# Encoder_BR.net
KiCad netlist of a schematic drawn in Altium Designer
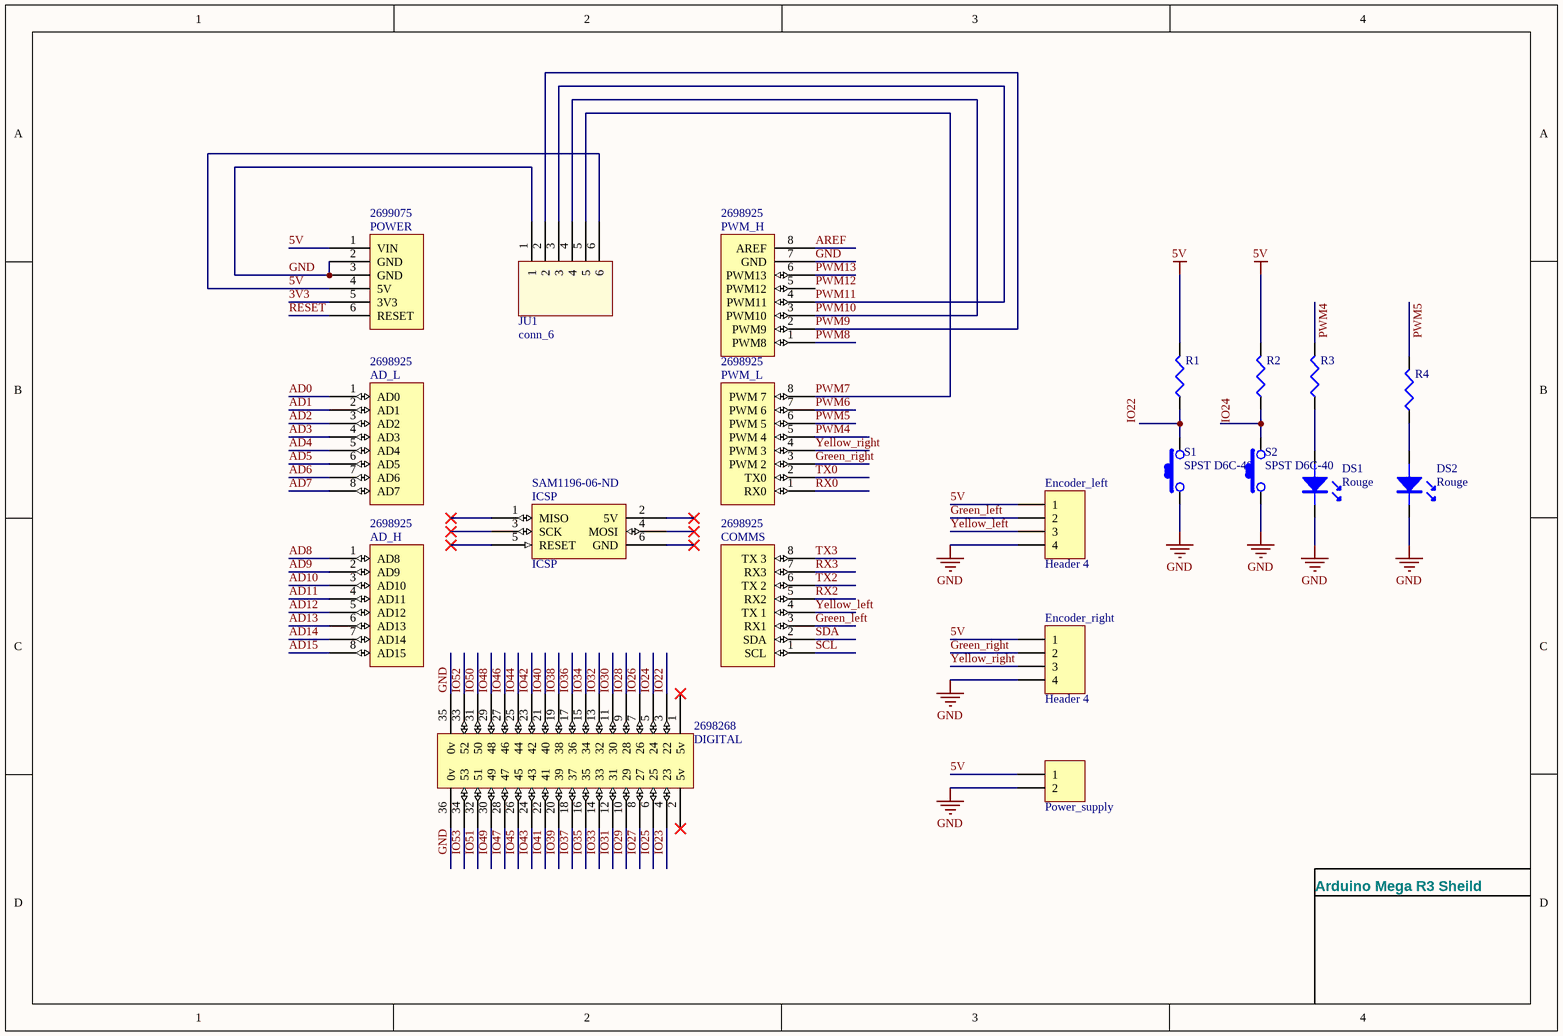
[diagram p0: Encoder_BR.SchDoc]

(export (version "E")
  (design (tool "Eeschema 10.0.6"))
  (components
    (comp (ref "AD_H")
      (value "AD_H")
      (footprint "Header 8x1 8.5mm")
      (fields (field (name "SUPPLIER PART NUMBER 4") "2698925"))
      (libsource (lib "Header") (part "AD_H"))
    )
    (comp (ref "AD_L")
      (value "AD_L")
      (footprint "Header 8x1 8.5mm")
      (fields (field (name "SUPPLIER PART NUMBER 5") "2698925"))
      (libsource (lib "Header") (part "AD_L"))
    )
    (comp (ref "COMMS")
      (value "Communication")
      (footprint "Header 8x1 8.5mm")
      (fields (field (name "SUPPLIER PART NUMBER 4") "2698925"))
      (libsource (lib "Header") (part "Communication"))
    )
    (comp (ref "DIGITAL")
      (value "IO_36")
      (footprint "HEADER 36X 8MM")
      (fields (field (name "SUPPLIER PART NUMBER 5") "2698268"))
      (libsource (lib "Header") (part "IO_36"))
    )
    (comp (ref "DS1")
      (value "LED")
      (footprint "LED 0.1")
      (fields (field (name "COLOR") "Rouge") (field (name "DESIGNER") "ECAM 2004"))
      (libsource (lib "ECAM") (part "LED"))
    )
    (comp (ref "DS2")
      (value "LED")
      (footprint "LED 0.1")
      (fields (field (name "COLOR") "Rouge") (field (name "DESIGNER") "ECAM 2004"))
      (libsource (lib "ECAM") (part "LED"))
    )
    (comp (ref "Encoder_left")
      (value "Header 4")
      (footprint "Header_4")
      (description "Header, 4-Pin")
      (fields (field (name "PUBLISHER") "Altium Limited"))
      (libsource (lib "Eurobot_lib") (part "Header 4"))
    )
    (comp (ref "Encoder_right")
      (value "Header 4")
      (footprint "Header_4")
      (description "Header, 4-Pin")
      (fields (field (name "PUBLISHER") "Altium Limited"))
      (libsource (lib "Eurobot_lib") (part "Header 4"))
    )
    (comp (ref "ICSP")
      (value "ICSP")
      (footprint "ICSP")
      (fields (field (name "SUPPLIER PART NUMBER 5") "SAM1196-06-ND"))
      (libsource (lib "Header") (part "ICSP"))
    )
    (comp (ref "JU1")
      (value "conn_6")
      (footprint "conn_6")
      (libsource (lib "Integrated_Library2") (part "conn_6"))
    )
    (comp (ref "POWER")
      (value "POWER")
      (footprint "Header 6x1 8.5mm")
      (fields (field (name "SUPPLIER PART NUMBER 2") "2699075"))
      (libsource (lib "Header") (part "POWER"))
    )
    (comp (ref "Power_supply")
      (value "Connecteur 2")
      (footprint "Header_2")
      (description "Header 2")
      (fields (field (name "DESIGNER") "ECAM 2005"))
      (libsource (lib "Eurobot_lib") (part "Connecteur 2"))
    )
    (comp (ref "PWM_H")
      (value "PWM_H")
      (footprint "Header 8x1 8.5mm")
      (fields (field (name "SUPPLIER PART NUMBER 4") "2698925"))
      (libsource (lib "Header") (part "PWM_H"))
    )
    (comp (ref "PWM_L")
      (value "PWM_L")
      (footprint "Header 8x1 8.5mm")
      (fields (field (name "SUPPLIER PART NUMBER 4") "2698925"))
      (libsource (lib "Header") (part "PWM_L"))
    )
    (comp (ref "R1")
      (value "Résistance")
      (footprint "AXIAL-0.3")
      (description "Résistance standard")
      (fields (field (name "DESIGNER") "ECAM 2005"))
      (libsource (lib "ECAM") (part "Résistance"))
    )
    (comp (ref "R2")
      (value "Résistance")
      (footprint "AXIAL-0.3")
      (description "Résistance standard")
      (fields (field (name "DESIGNER") "ECAM 2005"))
      (libsource (lib "ECAM") (part "Résistance"))
    )
    (comp (ref "R3")
      (value "Résistance")
      (footprint "AXIAL-0.3")
      (description "Résistance standard")
      (fields (field (name "DESIGNER") "ECAM 2005"))
      (libsource (lib "ECAM") (part "Résistance"))
    )
    (comp (ref "R4")
      (value "Résistance")
      (footprint "AXIAL-0.3")
      (description "Résistance standard")
      (fields (field (name "DESIGNER") "ECAM 2005"))
      (libsource (lib "ECAM") (part "Résistance"))
    )
    (comp (ref "S1")
      (value "Bouton Poussoir D6")
      (footprint "BP-D6 SPST")
      (description "Bouton poussoir")
      (fields
        (field (name "MANUFACTURER") "ITT CANON")
        (field (name "TYPE") "SPST D6C-40")
        (field (name "DESIGNER") "ECAM 2004")
      )
      (libsource (lib "ECAM") (part "Bouton Poussoir D6"))
    )
    (comp (ref "S2")
      (value "Bouton Poussoir D6")
      (footprint "BP-D6 SPST")
      (description "Bouton poussoir")
      (fields
        (field (name "MANUFACTURER") "ITT CANON")
        (field (name "TYPE") "SPST D6C-40")
        (field (name "DESIGNER") "ECAM 2004")
      )
      (libsource (lib "ECAM") (part "Bouton Poussoir D6"))
    )
  )
  (nets
    (net (code "1") (name "/3V3") (class "Default")
      (node (ref "POWER") (pin "5") (pinfunction "3V3_5") (pintype "power_in"))
    )
    (net (code "2") (name "/AD0") (class "Default")
      (node (ref "AD_L") (pin "1") (pinfunction "AD0_1") (pintype "bidirectional"))
    )
    (net (code "3") (name "/AD1") (class "Default")
      (node (ref "AD_L") (pin "2") (pinfunction "AD1_2") (pintype "bidirectional"))
    )
    (net (code "4") (name "/AD2") (class "Default")
      (node (ref "AD_L") (pin "3") (pinfunction "AD2_3") (pintype "bidirectional"))
    )
    (net (code "5") (name "/AD3") (class "Default")
      (node (ref "AD_L") (pin "4") (pinfunction "AD3_4") (pintype "bidirectional"))
    )
    (net (code "6") (name "/AD4") (class "Default")
      (node (ref "AD_L") (pin "5") (pinfunction "AD4_5") (pintype "bidirectional"))
    )
    (net (code "7") (name "/AD5") (class "Default")
      (node (ref "AD_L") (pin "6") (pinfunction "AD5_6") (pintype "bidirectional"))
    )
    (net (code "8") (name "/AD6") (class "Default")
      (node (ref "AD_L") (pin "7") (pinfunction "AD6_7") (pintype "bidirectional"))
    )
    (net (code "9") (name "/AD7") (class "Default")
      (node (ref "AD_L") (pin "8") (pinfunction "AD7_8") (pintype "bidirectional"))
    )
    (net (code "10") (name "/AD8") (class "Default")
      (node (ref "AD_H") (pin "1") (pinfunction "AD8_1") (pintype "bidirectional"))
    )
    (net (code "11") (name "/AD9") (class "Default")
      (node (ref "AD_H") (pin "2") (pinfunction "AD9_2") (pintype "bidirectional"))
    )
    (net (code "12") (name "/AD10") (class "Default")
      (node (ref "AD_H") (pin "3") (pinfunction "AD10_3") (pintype "bidirectional"))
    )
    (net (code "13") (name "/AD11") (class "Default")
      (node (ref "AD_H") (pin "4") (pinfunction "AD11_4") (pintype "bidirectional"))
    )
    (net (code "14") (name "/AD12") (class "Default")
      (node (ref "AD_H") (pin "5") (pinfunction "AD12_5") (pintype "bidirectional"))
    )
    (net (code "15") (name "/AD13") (class "Default")
      (node (ref "AD_H") (pin "6") (pinfunction "AD13_6") (pintype "bidirectional"))
    )
    (net (code "16") (name "/AD14") (class "Default")
      (node (ref "AD_H") (pin "7") (pinfunction "AD14_7") (pintype "bidirectional"))
    )
    (net (code "17") (name "/AD15") (class "Default")
      (node (ref "AD_H") (pin "8") (pinfunction "AD15_8") (pintype "bidirectional"))
    )
    (net (code "18") (name "/AREF") (class "Default")
      (node (ref "PWM_H") (pin "8") (pinfunction "AREF_8") (pintype "passive"))
    )
    (net (code "19") (name "/Green_left") (class "Default")
      (node (ref "COMMS") (pin "3") (pinfunction "RX1_3") (pintype "bidirectional"))
      (node (ref "Encoder_left") (pin "2") (pinfunction "2_2") (pintype "passive"))
    )
    (net (code "20") (name "/Green_right") (class "Default")
      (node (ref "Encoder_right") (pin "2") (pinfunction "2_2") (pintype "passive"))
      (node (ref "PWM_L") (pin "3") (pinfunction "PWM_2_3") (pintype "bidirectional"))
    )
    (net (code "21") (name "/IO22") (class "Default")
      (node (ref "DIGITAL") (pin "3") (pinfunction "22_3") (pintype "bidirectional"))
      (node (ref "R1") (pin "1") (pinfunction "1_1") (pintype "passive"))
      (node (ref "S1") (pin "2") (pinfunction "2_2") (pintype "passive"))
    )
    (net (code "22") (name "/IO23") (class "Default")
      (node (ref "DIGITAL") (pin "4") (pinfunction "23_4") (pintype "bidirectional"))
    )
    (net (code "23") (name "/IO24") (class "Default")
      (node (ref "DIGITAL") (pin "5") (pinfunction "24_5") (pintype "bidirectional"))
      (node (ref "R2") (pin "1") (pinfunction "1_1") (pintype "passive"))
      (node (ref "S2") (pin "2") (pinfunction "2_2") (pintype "passive"))
    )
    (net (code "24") (name "/IO25") (class "Default")
      (node (ref "DIGITAL") (pin "6") (pinfunction "25_6") (pintype "bidirectional"))
    )
    (net (code "25") (name "/IO26") (class "Default")
      (node (ref "DIGITAL") (pin "7") (pinfunction "26_7") (pintype "bidirectional"))
    )
    (net (code "26") (name "/IO27") (class "Default")
      (node (ref "DIGITAL") (pin "8") (pinfunction "27_8") (pintype "bidirectional"))
    )
    (net (code "27") (name "/IO28") (class "Default")
      (node (ref "DIGITAL") (pin "9") (pinfunction "28_9") (pintype "bidirectional"))
    )
    (net (code "28") (name "/IO29") (class "Default")
      (node (ref "DIGITAL") (pin "10") (pinfunction "29_10") (pintype "bidirectional"))
    )
    (net (code "29") (name "/IO30") (class "Default")
      (node (ref "DIGITAL") (pin "11") (pinfunction "30_11") (pintype "bidirectional"))
    )
    (net (code "30") (name "/IO31") (class "Default")
      (node (ref "DIGITAL") (pin "12") (pinfunction "31_12") (pintype "bidirectional"))
    )
    (net (code "31") (name "/IO32") (class "Default")
      (node (ref "DIGITAL") (pin "13") (pinfunction "32_13") (pintype "bidirectional"))
    )
    (net (code "32") (name "/IO33") (class "Default")
      (node (ref "DIGITAL") (pin "14") (pinfunction "33_14") (pintype "bidirectional"))
    )
    (net (code "33") (name "/IO34") (class "Default")
      (node (ref "DIGITAL") (pin "15") (pinfunction "34_15") (pintype "bidirectional"))
    )
    (net (code "34") (name "/IO35") (class "Default")
      (node (ref "DIGITAL") (pin "16") (pinfunction "35_16") (pintype "bidirectional"))
    )
    (net (code "35") (name "/IO36") (class "Default")
      (node (ref "DIGITAL") (pin "17") (pinfunction "36_17") (pintype "bidirectional"))
    )
    (net (code "36") (name "/IO37") (class "Default")
      (node (ref "DIGITAL") (pin "18") (pinfunction "37_18") (pintype "bidirectional"))
    )
    (net (code "37") (name "/IO38") (class "Default")
      (node (ref "DIGITAL") (pin "19") (pinfunction "38_19") (pintype "bidirectional"))
    )
    (net (code "38") (name "/IO39") (class "Default")
      (node (ref "DIGITAL") (pin "20") (pinfunction "39_20") (pintype "bidirectional"))
    )
    (net (code "39") (name "/IO40") (class "Default")
      (node (ref "DIGITAL") (pin "21") (pinfunction "40_21") (pintype "bidirectional"))
    )
    (net (code "40") (name "/IO41") (class "Default")
      (node (ref "DIGITAL") (pin "22") (pinfunction "41_22") (pintype "bidirectional"))
    )
    (net (code "41") (name "/IO42") (class "Default")
      (node (ref "DIGITAL") (pin "23") (pinfunction "42_23") (pintype "bidirectional"))
    )
    (net (code "42") (name "/IO43") (class "Default")
      (node (ref "DIGITAL") (pin "24") (pinfunction "43_24") (pintype "bidirectional"))
    )
    (net (code "43") (name "/IO44") (class "Default")
      (node (ref "DIGITAL") (pin "25") (pinfunction "44_25") (pintype "bidirectional"))
    )
    (net (code "44") (name "/IO45") (class "Default")
      (node (ref "DIGITAL") (pin "26") (pinfunction "45_26") (pintype "bidirectional"))
    )
    (net (code "45") (name "/IO46") (class "Default")
      (node (ref "DIGITAL") (pin "27") (pinfunction "46_27") (pintype "bidirectional"))
    )
    (net (code "46") (name "/IO47") (class "Default")
      (node (ref "DIGITAL") (pin "28") (pinfunction "47_28") (pintype "bidirectional"))
    )
    (net (code "47") (name "/IO48") (class "Default")
      (node (ref "DIGITAL") (pin "29") (pinfunction "48_29") (pintype "bidirectional"))
    )
    (net (code "48") (name "/IO49") (class "Default")
      (node (ref "DIGITAL") (pin "30") (pinfunction "49_30") (pintype "bidirectional"))
    )
    (net (code "49") (name "/IO50") (class "Default")
      (node (ref "DIGITAL") (pin "31") (pinfunction "50_31") (pintype "bidirectional"))
    )
    (net (code "50") (name "/IO51") (class "Default")
      (node (ref "DIGITAL") (pin "32") (pinfunction "51_32") (pintype "bidirectional"))
    )
    (net (code "51") (name "/IO52") (class "Default")
      (node (ref "DIGITAL") (pin "33") (pinfunction "52_33") (pintype "bidirectional"))
    )
    (net (code "52") (name "/IO53") (class "Default")
      (node (ref "DIGITAL") (pin "34") (pinfunction "53_34") (pintype "bidirectional"))
    )
    (net (code "53") (name "/PWM4") (class "Default")
      (node (ref "PWM_L") (pin "5") (pinfunction "PWM_4_5") (pintype "bidirectional"))
      (node (ref "R3") (pin "2") (pinfunction "2_2") (pintype "passive"))
    )
    (net (code "54") (name "/PWM5") (class "Default")
      (node (ref "PWM_L") (pin "6") (pinfunction "PWM_5_6") (pintype "bidirectional"))
      (node (ref "R4") (pin "2") (pinfunction "2_2") (pintype "passive"))
    )
    (net (code "55") (name "/PWM6") (class "Default")
      (node (ref "PWM_L") (pin "7") (pinfunction "PWM_6_7") (pintype "bidirectional"))
    )
    (net (code "56") (name "/PWM7") (class "Default")
      (node (ref "JU1") (pin "5") (pinfunction "5_5") (pintype "passive"))
      (node (ref "PWM_L") (pin "8") (pinfunction "PWM_7_8") (pintype "bidirectional"))
    )
    (net (code "57") (name "/PWM8") (class "Default")
      (node (ref "PWM_H") (pin "1") (pinfunction "PWM8_1") (pintype "bidirectional"))
    )
    (net (code "58") (name "/PWM9") (class "Default")
      (node (ref "JU1") (pin "2") (pinfunction "2_2") (pintype "passive"))
      (node (ref "PWM_H") (pin "2") (pinfunction "PWM9_2") (pintype "bidirectional"))
    )
    (net (code "59") (name "/PWM10") (class "Default")
      (node (ref "JU1") (pin "4") (pinfunction "4_4") (pintype "passive"))
      (node (ref "PWM_H") (pin "3") (pinfunction "PWM10_3") (pintype "bidirectional"))
    )
    (net (code "60") (name "/PWM11") (class "Default")
      (node (ref "JU1") (pin "3") (pinfunction "3_3") (pintype "passive"))
      (node (ref "PWM_H") (pin "4") (pinfunction "PWM11_4") (pintype "bidirectional"))
    )
    (net (code "61") (name "/PWM12") (class "Default")
      (node (ref "PWM_H") (pin "5") (pinfunction "PWM12_5") (pintype "bidirectional"))
    )
    (net (code "62") (name "/PWM13") (class "Default")
      (node (ref "PWM_H") (pin "6") (pinfunction "PWM13_6") (pintype "bidirectional"))
    )
    (net (code "63") (name "/RESET") (class "Default")
      (node (ref "POWER") (pin "6") (pinfunction "RESET_6") (pintype "passive"))
    )
    (net (code "64") (name "/RX0") (class "Default")
      (node (ref "PWM_L") (pin "1") (pinfunction "RX0_1") (pintype "bidirectional"))
    )
    (net (code "65") (name "/RX2") (class "Default")
      (node (ref "COMMS") (pin "5") (pinfunction "RX2_5") (pintype "bidirectional"))
    )
    (net (code "66") (name "/RX3") (class "Default")
      (node (ref "COMMS") (pin "7") (pinfunction "RX3_7") (pintype "bidirectional"))
    )
    (net (code "67") (name "/SCL") (class "Default")
      (node (ref "COMMS") (pin "1") (pinfunction "SCL_1") (pintype "bidirectional"))
    )
    (net (code "68") (name "/SDA") (class "Default")
      (node (ref "COMMS") (pin "2") (pinfunction "SDA_2") (pintype "bidirectional"))
    )
    (net (code "69") (name "/TX0") (class "Default")
      (node (ref "PWM_L") (pin "2") (pinfunction "TX0_2") (pintype "bidirectional"))
    )
    (net (code "70") (name "/TX2") (class "Default")
      (node (ref "COMMS") (pin "6") (pinfunction "TX_2_6") (pintype "bidirectional"))
    )
    (net (code "71") (name "/TX3") (class "Default")
      (node (ref "COMMS") (pin "8") (pinfunction "TX_3_8") (pintype "bidirectional"))
    )
    (net (code "72") (name "/Yellow_left") (class "Default")
      (node (ref "COMMS") (pin "4") (pinfunction "TX_1_4") (pintype "bidirectional"))
      (node (ref "Encoder_left") (pin "3") (pinfunction "3_3") (pintype "passive"))
    )
    (net (code "73") (name "/Yellow_right") (class "Default")
      (node (ref "Encoder_right") (pin "3") (pinfunction "3_3") (pintype "passive"))
      (node (ref "PWM_L") (pin "4") (pinfunction "PWM_3_4") (pintype "bidirectional"))
    )
    (net (code "74") (name "5V") (class "Default")
      (node (ref "Encoder_left") (pin "1") (pinfunction "1_1") (pintype "passive"))
      (node (ref "Encoder_right") (pin "1") (pinfunction "1_1") (pintype "passive"))
      (node (ref "JU1") (pin "6") (pinfunction "6_6") (pintype "passive"))
      (node (ref "POWER") (pin "1") (pinfunction "VIN_1") (pintype "power_in"))
      (node (ref "POWER") (pin "4") (pinfunction "5V_4") (pintype "power_in"))
      (node (ref "Power_supply") (pin "1") (pinfunction "1_1") (pintype "passive"))
      (node (ref "R1") (pin "2") (pinfunction "2_2") (pintype "passive"))
      (node (ref "R2") (pin "2") (pinfunction "2_2") (pintype "passive"))
    )
    (net (code "75") (name "GND") (class "Default")
      (node (ref "DIGITAL") (pin "35") (pinfunction "0v_35") (pintype "power_in"))
      (node (ref "DIGITAL") (pin "36") (pinfunction "0v_36") (pintype "power_in"))
      (node (ref "DS1") (pin "2") (pinfunction "K_2") (pintype "passive"))
      (node (ref "DS2") (pin "2") (pinfunction "K_2") (pintype "passive"))
      (node (ref "Encoder_left") (pin "4") (pinfunction "4_4") (pintype "passive"))
      (node (ref "Encoder_right") (pin "4") (pinfunction "4_4") (pintype "passive"))
      (node (ref "JU1") (pin "1") (pinfunction "1_1") (pintype "passive"))
      (node (ref "POWER") (pin "2") (pinfunction "GND_2") (pintype "power_in"))
      (node (ref "POWER") (pin "3") (pinfunction "GND_3") (pintype "power_in"))
      (node (ref "PWM_H") (pin "7") (pinfunction "GND_7") (pintype "power_in"))
      (node (ref "Power_supply") (pin "2") (pinfunction "2_2") (pintype "passive"))
      (node (ref "S1") (pin "1") (pinfunction "1_1") (pintype "passive"))
      (node (ref "S2") (pin "1") (pinfunction "1_1") (pintype "passive"))
    )
    (net (code "76") (name "Net-(DS1-A)") (class "Default")
      (node (ref "DS1") (pin "1") (pinfunction "A_1") (pintype "passive"))
      (node (ref "R3") (pin "1") (pinfunction "1_1") (pintype "passive"))
    )
    (net (code "77") (name "Net-(DS2-A)") (class "Default")
      (node (ref "DS2") (pin "1") (pinfunction "A_1") (pintype "passive"))
      (node (ref "R4") (pin "1") (pinfunction "1_1") (pintype "passive"))
    )
    (net (code "78") (name "unconnected-(DIGITAL-5v-Pad1)") (class "Default")
      (node (ref "DIGITAL") (pin "1") (pinfunction "5v_1") (pintype "power_in+no_connect"))
    )
    (net (code "79") (name "unconnected-(DIGITAL-5v-Pad2)") (class "Default")
      (node (ref "DIGITAL") (pin "2") (pinfunction "5v_2") (pintype "power_in+no_connect"))
    )
    (net (code "80") (name "unconnected-(ICSP-5V-Pad2)") (class "Default")
      (node (ref "ICSP") (pin "2") (pinfunction "5V_2") (pintype "power_in+no_connect"))
    )
    (net (code "81") (name "unconnected-(ICSP-GND-Pad6)") (class "Default")
      (node (ref "ICSP") (pin "6") (pinfunction "GND_6") (pintype "power_in+no_connect"))
    )
    (net (code "82") (name "unconnected-(ICSP-MISO-Pad1)") (class "Default")
      (node (ref "ICSP") (pin "1") (pinfunction "MISO_1") (pintype "bidirectional+no_connect"))
    )
    (net (code "83") (name "unconnected-(ICSP-MOSI-Pad4)") (class "Default")
      (node (ref "ICSP") (pin "4") (pinfunction "MOSI_4") (pintype "bidirectional+no_connect"))
    )
    (net (code "84") (name "unconnected-(ICSP-RESET-Pad5)") (class "Default")
      (node (ref "ICSP") (pin "5") (pinfunction "RESET_5") (pintype "input+no_connect"))
    )
    (net (code "85") (name "unconnected-(ICSP-SCK-Pad3)") (class "Default")
      (node (ref "ICSP") (pin "3") (pinfunction "SCK_3") (pintype "bidirectional+no_connect"))
    )
  )
)
